# LDO.net
KiCad netlist of a schematic drawn in Altium Designer
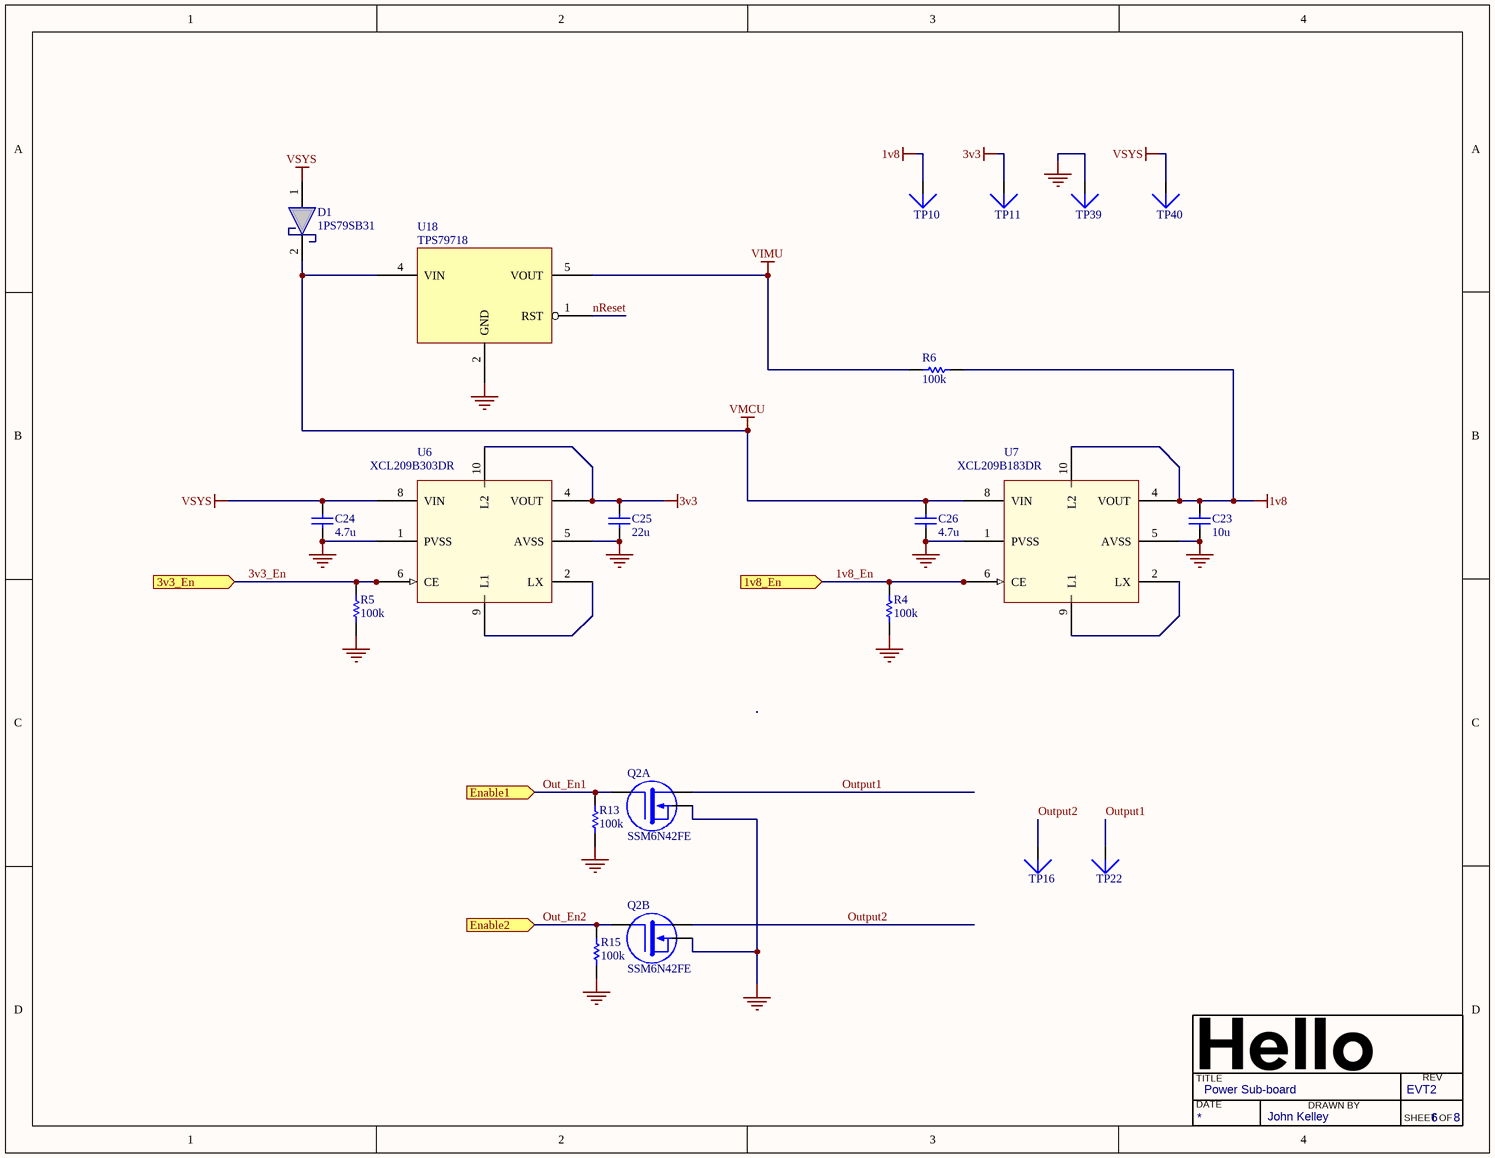
[diagram p0: LDO.SchDoc]

(export (version "E")
  (design (tool "Eeschema 10.0.6"))
  (components
    (comp (ref "C23")
      (value "10u")
      (footprint "CAP0603")
      (description "Chip capacitor")
      (fields (field (name "TOLERANCE") "10%") (field (name "VOLTAGE") "6.3V"))
      (libsource (lib "Hello") (part "C_10u_10_6.3_X5R_0603"))
    )
    (comp (ref "C24")
      (value "4.7u")
      (footprint "CAP0402")
      (description "Chip capacitor")
      (fields (field (name "TOLERANCE") "10%") (field (name "VOLTAGE") "10V"))
      (libsource (lib "Hello") (part "C_4.7u_10_10_JB_0402"))
    )
    (comp (ref "C25")
      (value "22u")
      (footprint "CAP0603")
      (description "Chip capacitor")
      (fields (field (name "TOLERANCE") "20%") (field (name "VOLTAGE") "10V"))
      (libsource (lib "Hello") (part "C_22u_10_20_JB_0603"))
    )
    (comp (ref "C26")
      (value "4.7u")
      (footprint "CAP0402")
      (description "Chip capacitor")
      (fields (field (name "TOLERANCE") "10%") (field (name "VOLTAGE") "10V"))
      (libsource (lib "Hello") (part "C_4.7u_10_10_JB_0402"))
    )
    (comp (ref "D1")
      (value "1PS79SB31")
      (footprint "SOD-523")
      (description "Schottky diode, 30V 200mA")
      (libsource (lib "Hello") (part "1PS79SB31"))
    )
    (comp (ref "Q2")
      (value "SSM6N42FE")
      (footprint "ES6")
      (description "Toshiba Dual N-Channel MOSFET 1.5v drive 20V 800ma")
      (libsource (lib "Hello") (part "SSM6N42FE"))
    )
    (comp (ref "R4")
      (value "100k")
      (footprint "RES0201")
      (description "Chip Resistor")
      (fields (field (name "TOLERANCE") "5 %") (field (name "POWER") "0.05 W"))
      (libsource (lib "Hello") (part "R_100k_5_0.05_0201"))
    )
    (comp (ref "R5")
      (value "100k")
      (footprint "RES0201")
      (description "Chip Resistor")
      (fields (field (name "TOLERANCE") "5 %") (field (name "POWER") "0.05 W"))
      (libsource (lib "Hello") (part "R_100k_5_0.05_0201"))
    )
    (comp (ref "R6")
      (value "100k")
      (footprint "RES0201")
      (description "Chip Resistor")
      (fields (field (name "TOLERANCE") "5 %") (field (name "POWER") "0.05 W"))
      (libsource (lib "Hello") (part "R_100k_5_0.05_0201"))
    )
    (comp (ref "R13")
      (value "100k")
      (footprint "RES0201")
      (description "Chip Resistor")
      (fields (field (name "TOLERANCE") "5 %") (field (name "POWER") "0.05 W"))
      (libsource (lib "Hello") (part "R_100k_5_0.05_0201"))
    )
    (comp (ref "R15")
      (value "100k")
      (footprint "RES0201")
      (description "Chip Resistor")
      (fields (field (name "TOLERANCE") "5 %") (field (name "POWER") "0.05 W"))
      (libsource (lib "Hello") (part "R_100k_5_0.05_0201"))
    )
    (comp (ref "TP10")
      (value "TestPoint")
      (footprint "TP-0.3")
      (description "Generic Test Point")
      (libsource (lib "Hello") (part "TestPoint"))
    )
    (comp (ref "TP11")
      (value "TestPoint")
      (footprint "TP-0.3")
      (description "Generic Test Point")
      (libsource (lib "Hello") (part "TestPoint"))
    )
    (comp (ref "TP16")
      (value "TestPoint")
      (footprint "TP-0.3")
      (description "Generic Test Point")
      (libsource (lib "Hello") (part "TestPoint"))
    )
    (comp (ref "TP22")
      (value "TestPoint")
      (footprint "TP-0.3")
      (description "Generic Test Point")
      (libsource (lib "Hello") (part "TestPoint"))
    )
    (comp (ref "TP39")
      (value "TestPoint")
      (footprint "TP-0.3")
      (description "Generic Test Point")
      (libsource (lib "Hello") (part "TestPoint"))
    )
    (comp (ref "TP40")
      (value "TestPoint")
      (footprint "TP-0.3")
      (description "Generic Test Point")
      (libsource (lib "Hello") (part "TestPoint"))
    )
    (comp (ref "U6")
      (value "XCL209B303DR")
      (footprint "USP-10B03")
      (description "Torex micro DC-DC Converter")
      (libsource (lib "Mopd") (part "XCL208"))
    )
    (comp (ref "U7")
      (value "XCL209B183DR")
      (footprint "USP-10B03")
      (description "Torex micro DC-DC Converter")
      (libsource (lib "Mopd") (part "XCL208"))
    )
    (comp (ref "U18")
      (value "TPS79718")
      (footprint "SOT65P212X110-5N")
      (description "LDO 1.8V SC70-5")
      (libsource (lib "dykes") (part "TPS79718DCK"))
    )
  )
  (nets
    (net (code "1") (name "/1v8_En") (class "Default")
      (node (ref "R4") (pin "1") (pinfunction "1_1") (pintype "passive"))
      (node (ref "U7") (pin "6") (pinfunction "CE_6") (pintype "input"))
    )
    (net (code "2") (name "/3v3_En") (class "Default")
      (node (ref "R5") (pin "2") (pinfunction "2_2") (pintype "passive"))
      (node (ref "U6") (pin "6") (pinfunction "CE_6") (pintype "input"))
    )
    (net (code "3") (name "/Out_En1") (class "Default")
      (node (ref "Q2") (pin "2") (pinfunction "G1_2") (pintype "passive"))
      (node (ref "R13") (pin "2") (pinfunction "2_2") (pintype "passive"))
    )
    (net (code "4") (name "/Out_En2") (class "Default")
      (node (ref "Q2") (pin "5") (pinfunction "G2_5") (pintype "passive"))
      (node (ref "R15") (pin "2") (pinfunction "2_2") (pintype "passive"))
    )
    (net (code "5") (name "/Output1") (class "Default")
      (node (ref "Q2") (pin "6") (pinfunction "D1_6") (pintype "passive"))
      (node (ref "TP22") (pin "1") (pinfunction "1_1") (pintype "passive"))
    )
    (net (code "6") (name "/Output2") (class "Default")
      (node (ref "Q2") (pin "3") (pinfunction "D2_3") (pintype "passive"))
      (node (ref "TP16") (pin "1") (pinfunction "1_1") (pintype "passive"))
    )
    (net (code "7") (name "/nReset") (class "Default")
      (node (ref "U18") (pin "1") (pinfunction "RST_1") (pintype "open_collector"))
    )
    (net (code "8") (name "1v8") (class "Default")
      (node (ref "C23") (pin "2") (pinfunction "2_2") (pintype "passive"))
      (node (ref "R6") (pin "2") (pinfunction "2_2") (pintype "passive"))
      (node (ref "TP10") (pin "1") (pinfunction "1_1") (pintype "passive"))
      (node (ref "U7") (pin "10") (pinfunction "L2_10") (pintype "passive"))
      (node (ref "U7") (pin "4") (pinfunction "VOUT_4") (pintype "power_in"))
    )
    (net (code "9") (name "3v3") (class "Default")
      (node (ref "C25") (pin "2") (pinfunction "2_2") (pintype "passive"))
      (node (ref "TP11") (pin "1") (pinfunction "1_1") (pintype "passive"))
      (node (ref "U6") (pin "10") (pinfunction "L2_10") (pintype "passive"))
      (node (ref "U6") (pin "4") (pinfunction "VOUT_4") (pintype "power_in"))
    )
    (net (code "10") (name "GND") (class "Default")
      (node (ref "C23") (pin "1") (pinfunction "1_1") (pintype "passive"))
      (node (ref "C24") (pin "1") (pinfunction "1_1") (pintype "passive"))
      (node (ref "C25") (pin "1") (pinfunction "1_1") (pintype "passive"))
      (node (ref "C26") (pin "1") (pinfunction "1_1") (pintype "passive"))
      (node (ref "Q2") (pin "1") (pinfunction "S1_1") (pintype "passive"))
      (node (ref "Q2") (pin "4") (pinfunction "S2_4") (pintype "passive"))
      (node (ref "R13") (pin "1") (pinfunction "1_1") (pintype "passive"))
      (node (ref "R15") (pin "1") (pinfunction "1_1") (pintype "passive"))
      (node (ref "R4") (pin "2") (pinfunction "2_2") (pintype "passive"))
      (node (ref "R5") (pin "1") (pinfunction "1_1") (pintype "passive"))
      (node (ref "TP39") (pin "1") (pinfunction "1_1") (pintype "passive"))
      (node (ref "U18") (pin "2") (pinfunction "GND_2") (pintype "power_in"))
      (node (ref "U6") (pin "1") (pinfunction "PVSS_1") (pintype "power_in"))
      (node (ref "U6") (pin "5") (pinfunction "AVSS_5") (pintype "power_in"))
      (node (ref "U7") (pin "1") (pinfunction "PVSS_1") (pintype "power_in"))
      (node (ref "U7") (pin "5") (pinfunction "AVSS_5") (pintype "power_in"))
    )
    (net (code "11") (name "Net-(U6-L1)") (class "Default")
      (node (ref "U6") (pin "2") (pinfunction "LX_2") (pintype "passive"))
      (node (ref "U6") (pin "9") (pinfunction "L1_9") (pintype "passive"))
    )
    (net (code "12") (name "Net-(U7-L1)") (class "Default")
      (node (ref "U7") (pin "2") (pinfunction "LX_2") (pintype "passive"))
      (node (ref "U7") (pin "9") (pinfunction "L1_9") (pintype "passive"))
    )
    (net (code "13") (name "VIMU") (class "Default")
      (node (ref "R6") (pin "1") (pinfunction "1_1") (pintype "passive"))
      (node (ref "U18") (pin "5") (pinfunction "VOUT_5") (pintype "power_in"))
    )
    (net (code "14") (name "VMCU") (class "Default")
      (node (ref "C26") (pin "2") (pinfunction "2_2") (pintype "passive"))
      (node (ref "D1") (pin "2") (pinfunction "Cathode_2") (pintype "passive"))
      (node (ref "U18") (pin "4") (pinfunction "VIN_4") (pintype "power_in"))
      (node (ref "U7") (pin "8") (pinfunction "VIN_8") (pintype "power_in"))
    )
    (net (code "15") (name "VSYS") (class "Default")
      (node (ref "C24") (pin "2") (pinfunction "2_2") (pintype "passive"))
      (node (ref "D1") (pin "1") (pinfunction "Anode_1") (pintype "passive"))
      (node (ref "TP40") (pin "1") (pinfunction "1_1") (pintype "passive"))
      (node (ref "U6") (pin "8") (pinfunction "VIN_8") (pintype "power_in"))
    )
  )
)
